# TPS54336ADDA.net
KiCad netlist of a schematic drawn in Altium Designer
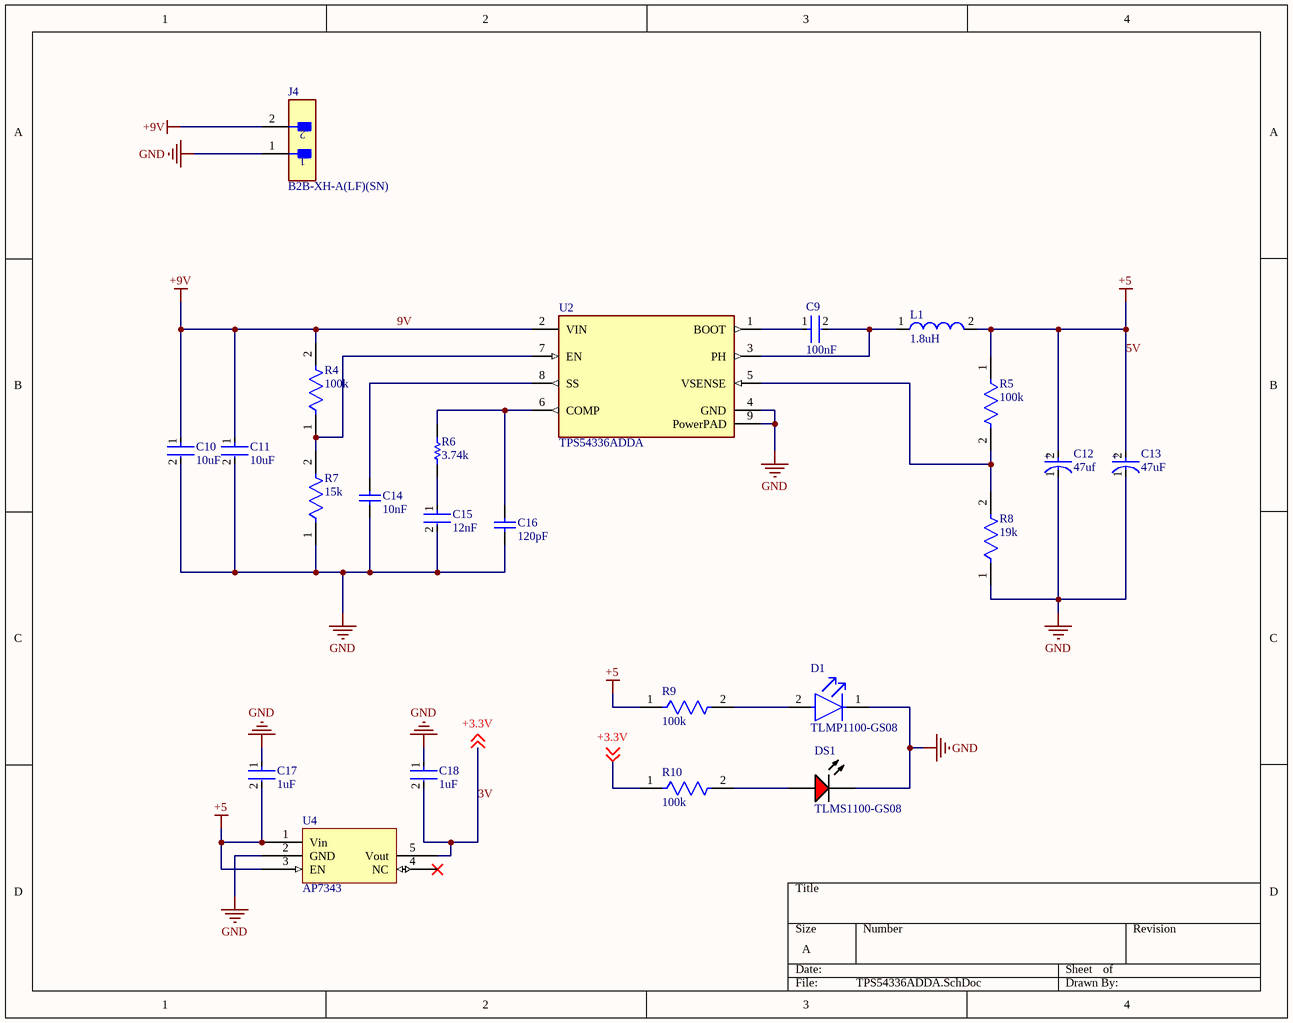
[diagram p0: TPS54336ADDA.SchDoc]

(export (version "E")
  (design (tool "Eeschema 10.0.6"))
  (components
    (comp (ref "C9")
      (value "100nF")
      (footprint "FP-CGA3E-0_3-0_1-IPC_A")
      (description "Cap Ceramic 100nF 50V X7R 10% Pad SMD 0603 +125°C Automotive T/R")
      (fields (field (name "TOLERANCE") "10%") (field (name "VOLTAGE") "50V"))
      (libsource (lib "Altium Content Vault") (part "b4654b650e69147ec39a6b967a45e02"))
    )
    (comp (ref "C10")
      (value "10uF")
      (footprint "FP-GRM188-0_2-MFG")
      (description "Chip Multilayer Ceramic Capacitors for General Purpose, 0603, 10uF, X5R, 15%, 20%, 25V")
      (fields (field (name "TOLERANCE") "20%") (field (name "VOLTAGE") "25V"))
      (libsource (lib "Altium Content Vault") (part "11868f565c42a9108669ba33697ecf6"))
    )
    (comp (ref "C11")
      (value "10uF")
      (footprint "FP-GRM188-0_2-MFG")
      (description "Chip Multilayer Ceramic Capacitors for General Purpose, 0603, 10uF, X5R, 15%, 20%, 25V")
      (fields (field (name "TOLERANCE") "20%") (field (name "VOLTAGE") "25V"))
      (libsource (lib "Altium Content Vault") (part "11868f565c42a9108669ba33697ecf6"))
    )
    (comp (ref "C12")
      (value "47uf")
      (footprint "FP-T491D476K025AT-MFG")
      (description "CAP TANT 47UF 10% 25V 2917")
      (fields (field (name "VOLTAGE") "25V") (field (name "TOLERANCE") "10%"))
      (libsource (lib "Altium Content Vault") (part "203bc49f2ac43e59fd269a8c329ed05"))
    )
    (comp (ref "C13")
      (value "47uF")
      (footprint "FP-T491D476K025AT-MFG")
      (description "CAP TANT 47UF 10% 25V 2917")
      (fields (field (name "VOLTAGE") "25V") (field (name "TOLERANCE") "10%"))
      (libsource (lib "Altium Content Vault") (part "203bc49f2ac43e59fd269a8c329ed05"))
    )
    (comp (ref "C14")
      (value "10nF")
      (footprint "CAPC1608X90X35ML10T15")
      (description "Chip Capacitor, 10 nF, +/- 10%, 50 V, -55 to 125 degC, 0603 (1608 Metric), RoHS, Tape and Reel")
      (fields (field (name "VOLTAGE") "50V") (field (name "TOLERANCE") "10%"))
      (libsource (lib "Altium Content Vault") (part "CAP-NP-2"))
    )
    (comp (ref "C15")
      (value "12nF")
      (footprint "FP-C0603C-CF-MFG")
      (description "CAP CER 0.012UF 50V 10% X7R 0603")
      (fields (field (name "MANUFACTURER") "KEMET") (field (name "TOLERANCE") "0.1"))
      (libsource (lib "Altium Content Vault") (part "b4654b650e69147ec39a6b967a45e02"))
    )
    (comp (ref "C16")
      (value "120pF")
      (footprint "CAPC1608X87X35NL15T15")
      (fields (field (name "MANUFACTURER") "Kemet") (field (name "PART NUMBER") "C0603C121J5GACTU"))
      (libsource (lib "Altium Content Vault") (part "CAP"))
    )
    (comp (ref "C17")
      (value "1uF")
      (footprint "FP-0603-L_1_6_0_1-W_0_8_0-IPC_B")
      (description "None")
      (fields (field (name "TOLERANCE") "10%"))
      (libsource (lib "Altium Content Vault") (part "02cd4be3c70576c341d710602a673aa"))
    )
    (comp (ref "C18")
      (value "1uF")
      (footprint "FP-0603-L_1_6_0_1-W_0_8_0-IPC_B")
      (description "None")
      (fields (field (name "TOLERANCE") "10%"))
      (libsource (lib "Altium Content Vault") (part "02cd4be3c70576c341d710602a673aa"))
    )
    (comp (ref "D1")
      (value "TLMP1100-GS08")
      (footprint "FP-6_541-5056_01-4-MFG")
      (description "LED GREEN 0603 SMD")
      (fields
        (field (name "MANUFACTURER") "Vishay")
        (field (name "OCTOPART") "https://octopart.com/tlmp1100-gs08-vishay-55433993")
      )
      (libsource (lib "Altium Content Vault") (part "8706943c75ba83719d021d2fdc84c58"))
    )
    (comp (ref "DS1")
      (value "TLMS1100-GS08")
      (footprint "VISH-TLMX1100_V")
      (description "LED, RED, 2.1 V, -40 to 100 degC, 2-Pin SMD (0603), RoHS, Tape and Reel")
      (fields (field (name "TOLERANCE") "5%"))
      (libsource (lib "Altium Content Vault") (part "LED-RED-AK-2"))
    )
    (comp (ref "J4")
      (value "B2B-XH-A(LF)(SN)")
      (footprint "FP-B2B-XH-A_LF_SN-MFG")
      (description "CONN HEADER VERT 2POS 2.5MM")
      (libsource (lib "Altium Content Vault") (part "3bc925449376181038e59eaffc5286c"))
    )
    (comp (ref "L1")
      (value "1.8uH")
      (footprint "WE-PDF-1045")
      (description "SMD Power Inductor WE-PDF, L = 1.80 µH")
      (libsource (lib "Altium Content Vault") (part "PAS-IND-INDUCTOR-2"))
    )
    (comp (ref "R4")
      (value "100k")
      (footprint "FP-RC0603-0_55-MFG")
      (description "RES SMD 100K OHM 1% 1/10W 0603")
      (fields (field (name "TOLERANCE") "1%"))
      (libsource (lib "Altium Content Vault") (part "1029c3af85768c4190bb7ad29bc67b5"))
    )
    (comp (ref "R5")
      (value "100k")
      (footprint "FP-ERA3A-IPC_A")
      (description "RES SMD 100K OHM 0.1% 1/10W 0603")
      (fields (field (name "TOLERANCE") "0.1%"))
      (libsource (lib "Altium Content Vault") (part "1029c3af85768c4190bb7ad29bc67b5"))
    )
    (comp (ref "R6")
      (value "3.74k")
      (footprint "RESC1608X55X30ML15T15")
      (fields (field (name "PART NUMBER") "ERJ-3EKF3741V") (field (name "MANUFACTURER") "Panasonic"))
      (libsource (lib "Altium Content Vault") (part "RES"))
    )
    (comp (ref "R7")
      (value "15k")
      (footprint "FP-CRCW0603-e3-MFG")
      (description "RES Thick Film, 15kΩ, 1%, 0.1W, 100ppm/°C, 0603")
      (fields (field (name "TOLERANCE") "1%"))
      (libsource (lib "Altium Content Vault") (part "1029c3af85768c4190bb7ad29bc67b5"))
    )
    (comp (ref "R8")
      (value "19k")
      (footprint "FP-CRCW0603-e3-IPC_A")
      (description "RES Thick Film, 18kΩ, 1%, 0.1W, 100ppm/°C, 0603")
      (fields (field (name "TOLERANCE") "1%"))
      (libsource (lib "Altium Content Vault") (part "1029c3af85768c4190bb7ad29bc67b5"))
    )
    (comp (ref "R9")
      (value "100k")
      (footprint "FP-ERA3A-IPC_A")
      (description "RES SMD 100K OHM 0.1% 1/10W 0603")
      (fields (field (name "TOLERANCE") "0.1%"))
      (libsource (lib "Altium Content Vault") (part "1029c3af85768c4190bb7ad29bc67b5"))
    )
    (comp (ref "R10")
      (value "100k")
      (footprint "FP-ERA3A-IPC_A")
      (description "RES SMD 100K OHM 0.1% 1/10W 0603")
      (fields (field (name "TOLERANCE") "0.1%"))
      (libsource (lib "Altium Content Vault") (part "1029c3af85768c4190bb7ad29bc67b5"))
    )
    (comp (ref "U2")
      (value "TPS54336ADDA")
      (footprint "FP-DDA0008E-IPC_C")
      (description "IC REG BUCK ADJUSTABLE 3A 8SOPWR")
      (libsource (lib "Altium Content Vault") (part "ec1f7ff2d6d9caf8daf3cb251107d25"))
    )
    (comp (ref "U4")
      (value "AP7343")
      (footprint "SOT95P245X110-5N")
      (libsource (lib "AP7343") (part "Component_2"))
    )
  )
  (nets
    (net (code "1") (name "+3.3V") (class "Default")
      (node (ref "C18") (pin "2") (pinfunction "2_2") (pintype "passive"))
      (node (ref "R10") (pin "1") (pinfunction "1_1") (pintype "passive"))
      (node (ref "U4") (pin "5") (pinfunction "Vout_5") (pintype "power_in"))
    )
    (net (code "2") (name "+5") (class "Default")
      (node (ref "C12") (pin "2") (pinfunction "A_2") (pintype "passive"))
      (node (ref "C13") (pin "2") (pinfunction "A_2") (pintype "passive"))
      (node (ref "C17") (pin "2") (pinfunction "2_2") (pintype "passive"))
      (node (ref "L1") (pin "2") (pinfunction "2_2") (pintype "passive"))
      (node (ref "R5") (pin "1") (pinfunction "1_1") (pintype "passive"))
      (node (ref "R9") (pin "1") (pinfunction "1_1") (pintype "passive"))
      (node (ref "U4") (pin "1") (pinfunction "Vin_1") (pintype "power_in"))
      (node (ref "U4") (pin "3") (pinfunction "EN_3") (pintype "input"))
    )
    (net (code "3") (name "+9V") (class "Default")
      (node (ref "C10") (pin "1") (pinfunction "1_1") (pintype "passive"))
      (node (ref "C11") (pin "1") (pinfunction "1_1") (pintype "passive"))
      (node (ref "J4") (pin "2") (pinfunction "2_2") (pintype "passive"))
      (node (ref "R4") (pin "2") (pinfunction "2_2") (pintype "passive"))
      (node (ref "U2") (pin "2") (pinfunction "VIN_2") (pintype "power_in"))
    )
    (net (code "4") (name "GND") (class "Default")
      (node (ref "C10") (pin "2") (pinfunction "2_2") (pintype "passive"))
      (node (ref "C11") (pin "2") (pinfunction "2_2") (pintype "passive"))
      (node (ref "C12") (pin "1") (pinfunction "C_1") (pintype "passive"))
      (node (ref "C13") (pin "1") (pinfunction "C_1") (pintype "passive"))
      (node (ref "C14") (pin "1") (pinfunction "1_1") (pintype "passive"))
      (node (ref "C15") (pin "2") (pinfunction "2_2") (pintype "passive"))
      (node (ref "C16") (pin "1") (pinfunction "1_1") (pintype "passive"))
      (node (ref "C17") (pin "1") (pinfunction "1_1") (pintype "passive"))
      (node (ref "C18") (pin "1") (pinfunction "1_1") (pintype "passive"))
      (node (ref "D1") (pin "1") (pinfunction "C_1") (pintype "passive"))
      (node (ref "DS1") (pin "2") (pinfunction "K_2") (pintype "passive"))
      (node (ref "J4") (pin "1") (pinfunction "1_1") (pintype "passive"))
      (node (ref "R7") (pin "1") (pinfunction "1_1") (pintype "passive"))
      (node (ref "R8") (pin "1") (pinfunction "1_1") (pintype "passive"))
      (node (ref "U2") (pin "4") (pinfunction "GND_4") (pintype "power_in"))
      (node (ref "U2") (pin "9") (pinfunction "PowerPAD_9") (pintype "power_in"))
      (node (ref "U4") (pin "2") (pinfunction "GND_2") (pintype "power_in"))
    )
    (net (code "5") (name "Net-(C15-Pad1)") (class "Default")
      (node (ref "C15") (pin "1") (pinfunction "1_1") (pintype "passive"))
      (node (ref "R6") (pin "1") (pinfunction "1_1") (pintype "passive"))
    )
    (net (code "6") (name "Net-(D1-A)") (class "Default")
      (node (ref "D1") (pin "2") (pinfunction "A_2") (pintype "passive"))
      (node (ref "R9") (pin "2") (pinfunction "2_2") (pintype "passive"))
    )
    (net (code "7") (name "Net-(DS1-A)") (class "Default")
      (node (ref "DS1") (pin "1") (pinfunction "A_1") (pintype "passive"))
      (node (ref "R10") (pin "2") (pinfunction "2_2") (pintype "passive"))
    )
    (net (code "8") (name "Net-(U2-BOOT)") (class "Default")
      (node (ref "C9") (pin "1") (pinfunction "1_1") (pintype "passive"))
      (node (ref "U2") (pin "1") (pinfunction "BOOT_1") (pintype "output"))
    )
    (net (code "9") (name "Net-(U2-COMP)") (class "Default")
      (node (ref "C16") (pin "2") (pinfunction "2_2") (pintype "passive"))
      (node (ref "R6") (pin "2") (pinfunction "2_2") (pintype "passive"))
      (node (ref "U2") (pin "6") (pinfunction "COMP_6") (pintype "output"))
    )
    (net (code "10") (name "Net-(U2-EN)") (class "Default")
      (node (ref "R4") (pin "1") (pinfunction "1_1") (pintype "passive"))
      (node (ref "R7") (pin "2") (pinfunction "2_2") (pintype "passive"))
      (node (ref "U2") (pin "7") (pinfunction "EN_7") (pintype "input"))
    )
    (net (code "11") (name "Net-(U2-PH)") (class "Default")
      (node (ref "C9") (pin "2") (pinfunction "2_2") (pintype "passive"))
      (node (ref "L1") (pin "1") (pinfunction "1_1") (pintype "passive"))
      (node (ref "U2") (pin "3") (pinfunction "PH_3") (pintype "output"))
    )
    (net (code "12") (name "Net-(U2-SS)") (class "Default")
      (node (ref "C14") (pin "2") (pinfunction "2_2") (pintype "passive"))
      (node (ref "U2") (pin "8") (pinfunction "SS_8") (pintype "output"))
    )
    (net (code "13") (name "Net-(U2-VSENSE)") (class "Default")
      (node (ref "R5") (pin "2") (pinfunction "2_2") (pintype "passive"))
      (node (ref "R8") (pin "2") (pinfunction "2_2") (pintype "passive"))
      (node (ref "U2") (pin "5") (pinfunction "VSENSE_5") (pintype "input"))
    )
    (net (code "14") (name "unconnected-(U4-NC-Pad4)") (class "Default")
      (node (ref "U4") (pin "4") (pinfunction "NC_4") (pintype "bidirectional+no_connect"))
    )
  )
)
